# Serial.net
KiCad netlist of a schematic drawn in Altium Designer
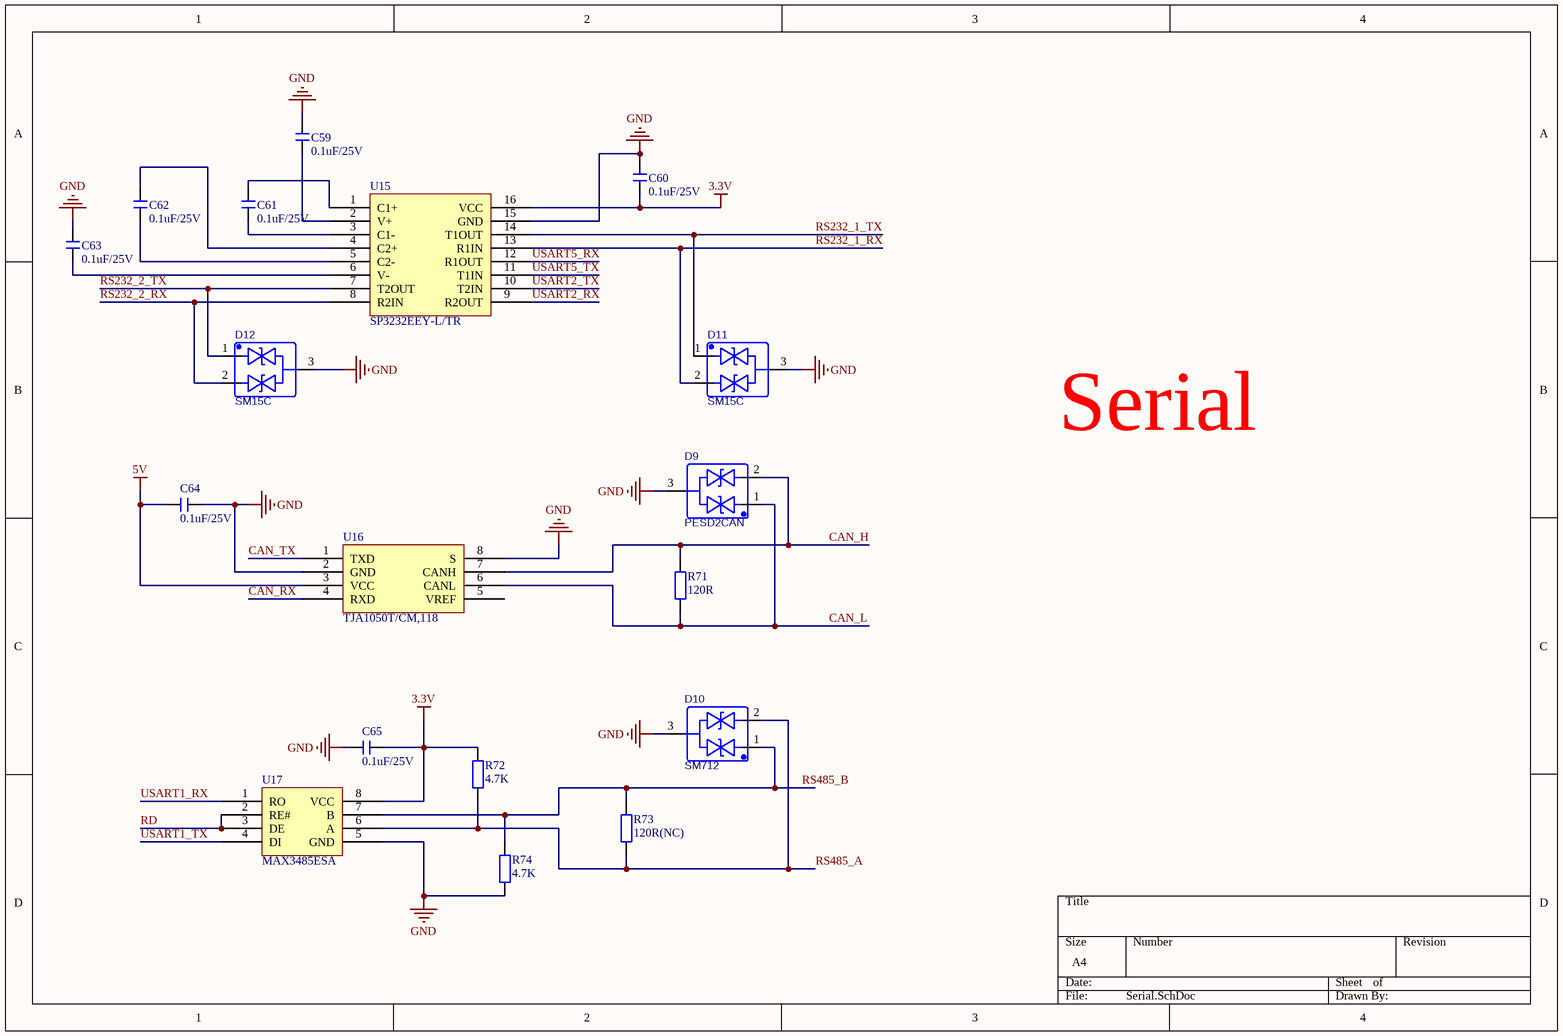
[diagram p0: Serial.SchDoc]

(export (version "E")
  (design (tool "Eeschema 10.0.6"))
  (components
    (comp (ref "C59")
      (value "0.1uF/25V")
      (footprint "C 0603_L")
      (description "无极性贴片电容")
      (fields (field (name "版权归属") "源创客"))
      (libsource (lib "电阻-电容-电感") (part "C"))
    )
    (comp (ref "C60")
      (value "0.1uF/25V")
      (footprint "C 0603_L")
      (description "无极性贴片电容")
      (fields (field (name "版权归属") "源创客"))
      (libsource (lib "电阻-电容-电感") (part "C"))
    )
    (comp (ref "C61")
      (value "0.1uF/25V")
      (footprint "C 0603_L")
      (description "无极性贴片电容")
      (fields (field (name "版权归属") "源创客"))
      (libsource (lib "电阻-电容-电感") (part "C"))
    )
    (comp (ref "C62")
      (value "0.1uF/25V")
      (footprint "C 0603_L")
      (description "无极性贴片电容")
      (fields (field (name "版权归属") "源创客"))
      (libsource (lib "电阻-电容-电感") (part "C"))
    )
    (comp (ref "C63")
      (value "0.1uF/25V")
      (footprint "C 0603_L")
      (description "无极性贴片电容")
      (fields (field (name "版权归属") "源创客"))
      (libsource (lib "电阻-电容-电感") (part "C"))
    )
    (comp (ref "C64")
      (value "0.1uF/25V")
      (footprint "C 0603_L")
      (description "无极性贴片电容")
      (fields (field (name "版权归属") "源创客"))
      (libsource (lib "电阻-电容-电感") (part "C"))
    )
    (comp (ref "C65")
      (value "0.1uF/25V")
      (footprint "C 0603_L")
      (description "无极性贴片电容")
      (fields (field (name "版权归属") "源创客"))
      (libsource (lib "电阻-电容-电感") (part "C"))
    )
    (comp (ref "D9")
      (value "PESD2CAN")
      (footprint "SOT23-3N")
      (fields (field (name "BOM_SUPPLIER PART") "C284078") (field (name "CONTRIBUTOR") "LCSC"))
      (libsource (lib "MICB") (part "PESD2CAN"))
    )
    (comp (ref "D10")
      (value "SM712")
      (footprint "SOT23-3N")
      (fields
        (field (name "BOM_SUPPLIER PART") "C284078")
        (field (name "BOM_MANUFACTURER PART") "PESD2CAN")
        (field (name "CONTRIBUTOR") "LCSC")
      )
      (libsource (lib "MICB") (part "PESD2CAN"))
    )
    (comp (ref "D11")
      (value "SM15C")
      (footprint "SOT23-3N")
      (fields
        (field (name "BOM_SUPPLIER PART") "C284078")
        (field (name "BOM_MANUFACTURER PART") "PESD2CAN")
        (field (name "CONTRIBUTOR") "LCSC")
      )
      (libsource (lib "MICB") (part "PESD2CAN"))
    )
    (comp (ref "D12")
      (value "SM15C")
      (footprint "SOT23-3N")
      (fields
        (field (name "BOM_SUPPLIER PART") "C284078")
        (field (name "BOM_MANUFACTURER PART") "PESD2CAN")
        (field (name "CONTRIBUTOR") "LCSC")
      )
      (libsource (lib "MICB") (part "PESD2CAN"))
    )
    (comp (ref "R71")
      (value "120R")
      (footprint "R 0603_L")
      (description "贴片电阻")
      (fields (field (name "版权归属") "源创客"))
      (libsource (lib "电阻-电容-电感") (part "R"))
    )
    (comp (ref "R72")
      (value "4.7K")
      (footprint "R 0603_L")
      (description "贴片电阻")
      (fields (field (name "版权归属") "源创客"))
      (libsource (lib "电阻-电容-电感") (part "R"))
    )
    (comp (ref "R73")
      (value "120R(NC)")
      (footprint "R 0603_L")
      (description "贴片电阻")
      (fields (field (name "版权归属") "源创客"))
      (libsource (lib "电阻-电容-电感") (part "R"))
    )
    (comp (ref "R74")
      (value "4.7K")
      (footprint "R 0603_L")
      (description "贴片电阻")
      (fields (field (name "版权归属") "源创客"))
      (libsource (lib "电阻-电容-电感") (part "R"))
    )
    (comp (ref "U15")
      (value "SP3232EEY-L/TR")
      (footprint "TSSOP16_N")
      (libsource (lib "MICB") (part "SP3232EEY-L/TR"))
    )
    (comp (ref "U16")
      (value "TJA1050T/CM,118")
      (footprint "SOP-8")
      (libsource (lib "MICB") (part "TJA1050T/CM,118"))
    )
    (comp (ref "U17") (value "MAX3485ESA") (footprint "SOP-8") (libsource (lib "MICB") (part "MAX3485ESA")))
  )
  (nets
    (net (code "1") (name "/CAN_H") (class "Default")
      (node (ref "D9") (pin "2") (pinfunction "2_2") (pintype "passive"))
      (node (ref "R71") (pin "2") (pinfunction "2_2") (pintype "passive"))
      (node (ref "U16") (pin "7") (pinfunction "CANH_7") (pintype "passive"))
    )
    (net (code "2") (name "/CAN_L") (class "Default")
      (node (ref "D9") (pin "1") (pinfunction "1_1") (pintype "passive"))
      (node (ref "R71") (pin "1") (pinfunction "1_1") (pintype "passive"))
      (node (ref "U16") (pin "6") (pinfunction "CANL_6") (pintype "passive"))
    )
    (net (code "3") (name "/CAN_RX") (class "Default")
      (node (ref "U16") (pin "4") (pinfunction "RXD_4") (pintype "passive"))
    )
    (net (code "4") (name "/CAN_TX") (class "Default")
      (node (ref "U16") (pin "1") (pinfunction "TXD_1") (pintype "passive"))
    )
    (net (code "5") (name "/RD") (class "Default")
      (node (ref "U17") (pin "2") (pinfunction "RE#_2") (pintype "passive"))
      (node (ref "U17") (pin "3") (pinfunction "DE_3") (pintype "passive"))
    )
    (net (code "6") (name "/RS232_1_RX") (class "Default")
      (node (ref "D11") (pin "2") (pinfunction "2_2") (pintype "passive"))
      (node (ref "U15") (pin "13") (pinfunction "R1IN_13") (pintype "passive"))
    )
    (net (code "7") (name "/RS232_1_TX") (class "Default")
      (node (ref "D11") (pin "1") (pinfunction "1_1") (pintype "passive"))
      (node (ref "U15") (pin "14") (pinfunction "T1OUT_14") (pintype "passive"))
    )
    (net (code "8") (name "/RS232_2_RX") (class "Default")
      (node (ref "D12") (pin "2") (pinfunction "2_2") (pintype "passive"))
      (node (ref "U15") (pin "8") (pinfunction "R2IN_8") (pintype "passive"))
    )
    (net (code "9") (name "/RS232_2_TX") (class "Default")
      (node (ref "D12") (pin "1") (pinfunction "1_1") (pintype "passive"))
      (node (ref "U15") (pin "7") (pinfunction "T2OUT_7") (pintype "passive"))
    )
    (net (code "10") (name "/RS485_A") (class "Default")
      (node (ref "D10") (pin "2") (pinfunction "2_2") (pintype "passive"))
      (node (ref "R72") (pin "1") (pinfunction "1_1") (pintype "passive"))
      (node (ref "R73") (pin "1") (pinfunction "1_1") (pintype "passive"))
      (node (ref "U17") (pin "6") (pinfunction "A_6") (pintype "passive"))
    )
    (net (code "11") (name "/RS485_B") (class "Default")
      (node (ref "D10") (pin "1") (pinfunction "1_1") (pintype "passive"))
      (node (ref "R73") (pin "2") (pinfunction "2_2") (pintype "passive"))
      (node (ref "R74") (pin "2") (pinfunction "2_2") (pintype "passive"))
      (node (ref "U17") (pin "7") (pinfunction "B_7") (pintype "passive"))
    )
    (net (code "12") (name "/USART1_RX") (class "Default")
      (node (ref "U17") (pin "1") (pinfunction "RO_1") (pintype "passive"))
    )
    (net (code "13") (name "/USART1_TX") (class "Default")
      (node (ref "U17") (pin "4") (pinfunction "DI_4") (pintype "passive"))
    )
    (net (code "14") (name "/USART2_RX") (class "Default")
      (node (ref "U15") (pin "9") (pinfunction "R2OUT_9") (pintype "passive"))
    )
    (net (code "15") (name "/USART2_TX") (class "Default")
      (node (ref "U15") (pin "10") (pinfunction "T2IN_10") (pintype "passive"))
    )
    (net (code "16") (name "/USART5_RX") (class "Default")
      (node (ref "U15") (pin "12") (pinfunction "R1OUT_12") (pintype "passive"))
    )
    (net (code "17") (name "/USART5_TX") (class "Default")
      (node (ref "U15") (pin "11") (pinfunction "T1IN_11") (pintype "passive"))
    )
    (net (code "18") (name "3.3V") (class "Default")
      (node (ref "C60") (pin "1") (pinfunction "1_1") (pintype "passive"))
      (node (ref "C65") (pin "1") (pinfunction "1_1") (pintype "passive"))
      (node (ref "R72") (pin "2") (pinfunction "2_2") (pintype "passive"))
      (node (ref "U15") (pin "16") (pinfunction "VCC_16") (pintype "passive"))
      (node (ref "U17") (pin "8") (pinfunction "VCC_8") (pintype "passive"))
    )
    (net (code "19") (name "5V") (class "Default")
      (node (ref "C64") (pin "1") (pinfunction "1_1") (pintype "passive"))
      (node (ref "U16") (pin "3") (pinfunction "VCC_3") (pintype "passive"))
    )
    (net (code "20") (name "GND") (class "Default")
      (node (ref "C59") (pin "2") (pinfunction "2_2") (pintype "passive"))
      (node (ref "C60") (pin "2") (pinfunction "2_2") (pintype "passive"))
      (node (ref "C63") (pin "2") (pinfunction "2_2") (pintype "passive"))
      (node (ref "C64") (pin "2") (pinfunction "2_2") (pintype "passive"))
      (node (ref "C65") (pin "2") (pinfunction "2_2") (pintype "passive"))
      (node (ref "D10") (pin "3") (pinfunction "3_3") (pintype "passive"))
      (node (ref "D11") (pin "3") (pinfunction "3_3") (pintype "passive"))
      (node (ref "D12") (pin "3") (pinfunction "3_3") (pintype "passive"))
      (node (ref "D9") (pin "3") (pinfunction "3_3") (pintype "passive"))
      (node (ref "R74") (pin "1") (pinfunction "1_1") (pintype "passive"))
      (node (ref "U15") (pin "15") (pinfunction "GND_15") (pintype "passive"))
      (node (ref "U16") (pin "2") (pinfunction "GND_2") (pintype "passive"))
      (node (ref "U16") (pin "8") (pinfunction "S_8") (pintype "passive"))
      (node (ref "U17") (pin "5") (pinfunction "GND_5") (pintype "passive"))
    )
    (net (code "21") (name "Net-(U15-C1+)") (class "Default")
      (node (ref "C61") (pin "2") (pinfunction "2_2") (pintype "passive"))
      (node (ref "U15") (pin "1") (pinfunction "C1+_1") (pintype "passive"))
    )
    (net (code "22") (name "Net-(U15-C1-)") (class "Default")
      (node (ref "C61") (pin "1") (pinfunction "1_1") (pintype "passive"))
      (node (ref "U15") (pin "3") (pinfunction "C1-_3") (pintype "passive"))
    )
    (net (code "23") (name "Net-(U15-C2+)") (class "Default")
      (node (ref "C62") (pin "2") (pinfunction "2_2") (pintype "passive"))
      (node (ref "U15") (pin "4") (pinfunction "C2+_4") (pintype "passive"))
    )
    (net (code "24") (name "Net-(U15-C2-)") (class "Default")
      (node (ref "C62") (pin "1") (pinfunction "1_1") (pintype "passive"))
      (node (ref "U15") (pin "5") (pinfunction "C2-_5") (pintype "passive"))
    )
    (net (code "25") (name "Net-(U15-V+)") (class "Default")
      (node (ref "C59") (pin "1") (pinfunction "1_1") (pintype "passive"))
      (node (ref "U15") (pin "2") (pinfunction "V+_2") (pintype "passive"))
    )
    (net (code "26") (name "Net-(U15-V-)") (class "Default")
      (node (ref "C63") (pin "1") (pinfunction "1_1") (pintype "passive"))
      (node (ref "U15") (pin "6") (pinfunction "V-_6") (pintype "passive"))
    )
    (net (code "27") (name "unconnected-(U16-VREF-Pad5)") (class "Default")
      (node (ref "U16") (pin "5") (pinfunction "VREF_5") (pintype "passive"))
    )
  )
)
